# sterownik.net
KiCad netlist of a schematic drawn in EAGLE
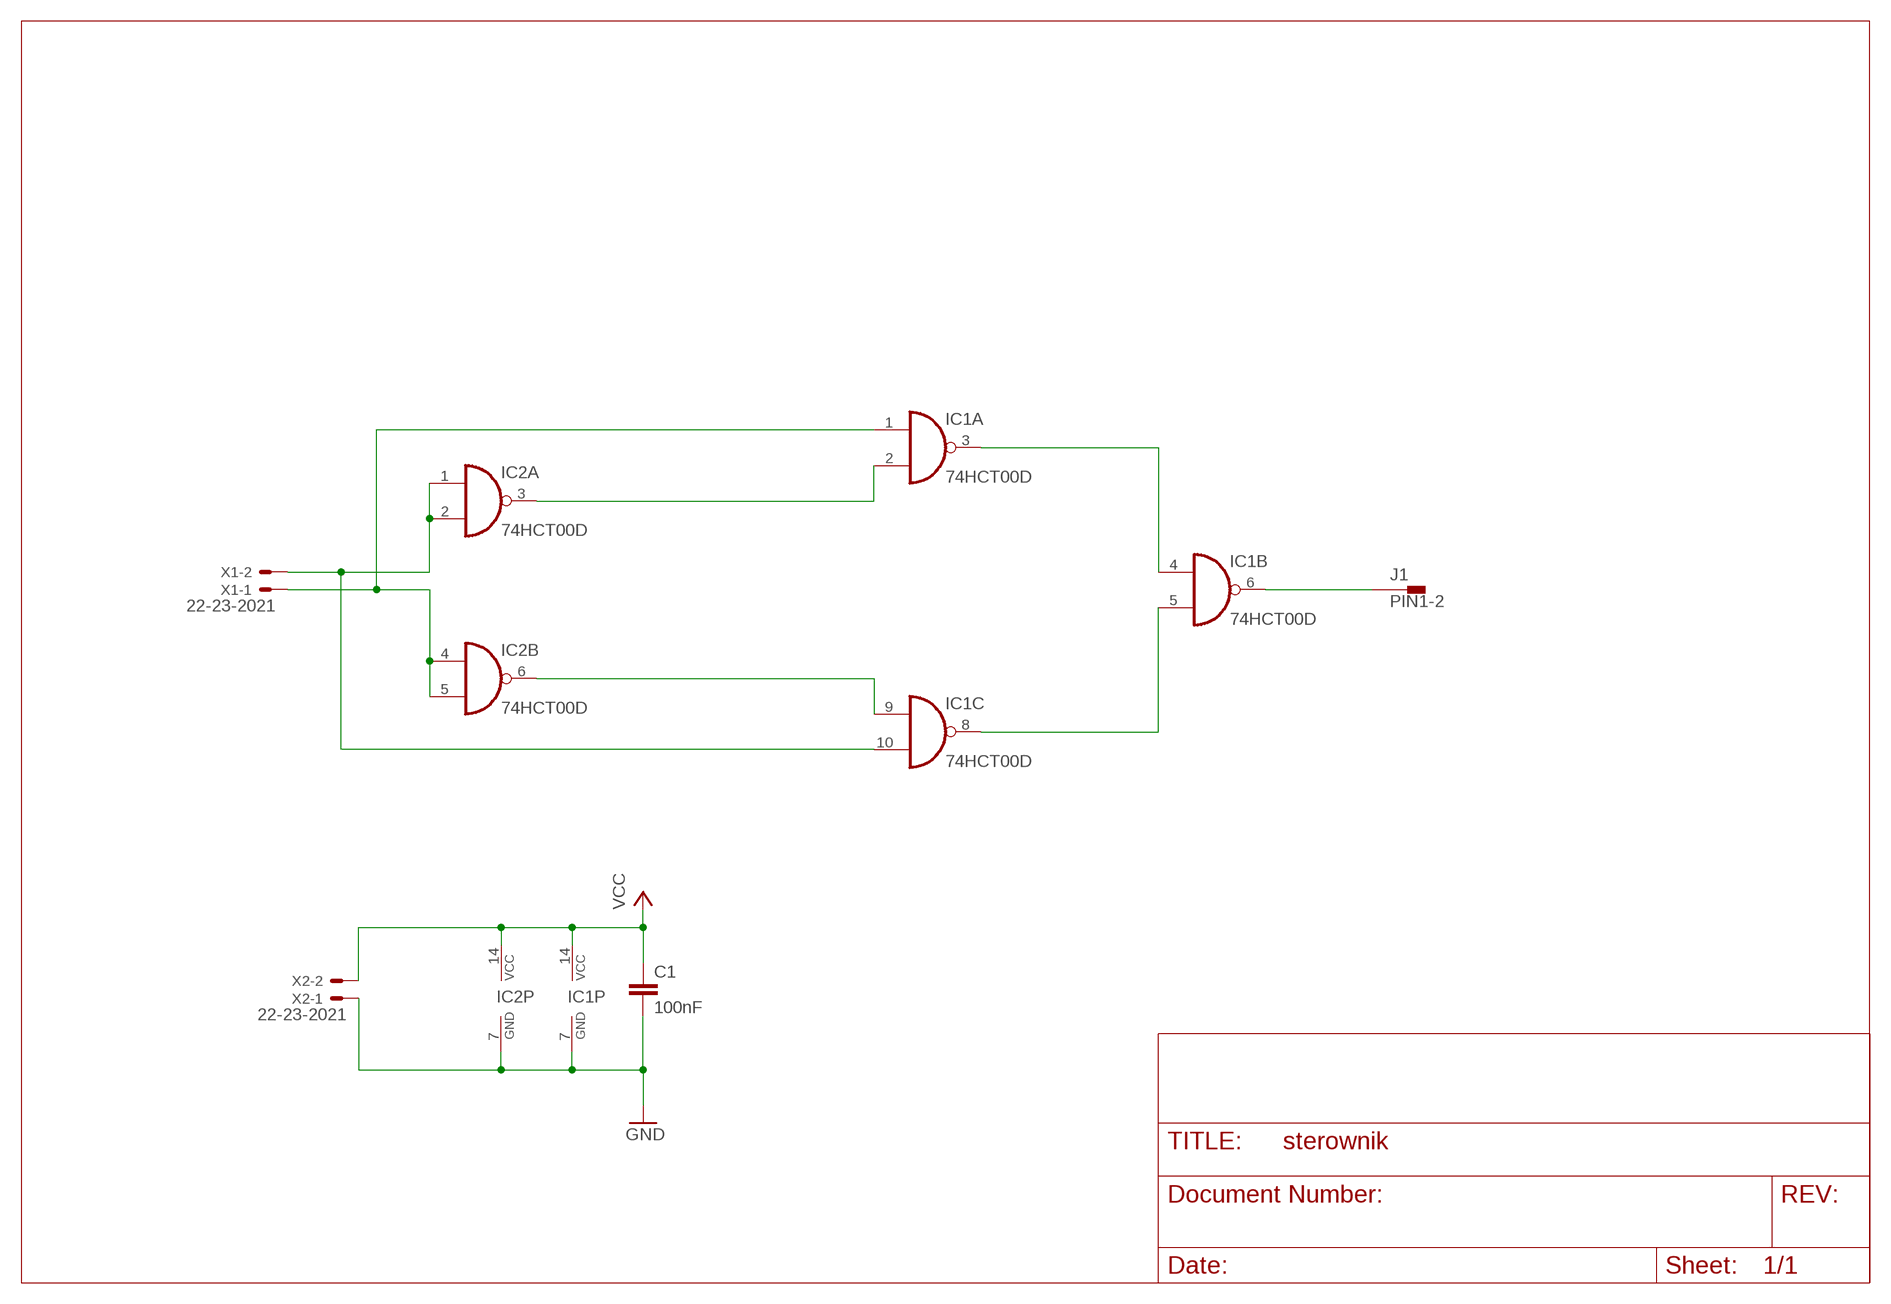
[diagram p0: schematic, sheet 1]

(export (version "E")
  (design (tool "Eeschema 10.0.6"))
  (components
    (comp (ref "C1")
      (value "100nF")
      (footprint "eagle-import:C025-024X044")
      (libsource (lib "eagle-import") (part "C-EU025-024X044"))
    )
    (comp (ref "IC1")
      (value "74HCT00D")
      (footprint "eagle-import:SO14")
      (libsource (lib "eagle-import") (part "7400DHCT"))
    )
    (comp (ref "IC2")
      (value "74HCT00D")
      (footprint "eagle-import:SO14")
      (libsource (lib "eagle-import") (part "7400DHCT"))
    )
    (comp (ref "J1")
      (value "PIN1-2")
      (footprint "eagle-import:62221")
      (fields (field (name "MF") "TYCO ELECTRONICS") (field (name "MPN") "62221-1"))
      (libsource (lib "eagle-import") (part "PIN1-2"))
    )
    (comp (ref "X1")
      (value "22-23-2021")
      (footprint "eagle-import:22-23-2021")
      (fields (field (name "MF") "MOLEX"))
      (libsource (lib "eagle-import") (part "22-23-2021"))
    )
    (comp (ref "X2")
      (value "22-23-2021")
      (footprint "eagle-import:22-23-2021")
      (fields (field (name "MF") "MOLEX"))
      (libsource (lib "eagle-import") (part "22-23-2021"))
    )
  )
  (nets
    (net (code "1") (name "GND") (class "Default")
      (node (ref "C1") (pin "2") (pinfunction "2_2") (pintype "passive"))
      (node (ref "IC1") (pin "7") (pinfunction "GND_7") (pintype "power_in"))
      (node (ref "IC2") (pin "7") (pinfunction "GND_7") (pintype "power_in"))
      (node (ref "X2") (pin "1") (pinfunction "S_1") (pintype "passive"))
    )
    (net (code "2") (name "Net-(IC1A-I0)") (class "Default")
      (node (ref "IC1") (pin "1") (pinfunction "I0_1") (pintype "input"))
      (node (ref "IC2") (pin "4") (pinfunction "I0_4") (pintype "input"))
      (node (ref "IC2") (pin "5") (pinfunction "I1_5") (pintype "input"))
      (node (ref "X1") (pin "1") (pinfunction "S_1") (pintype "passive"))
    )
    (net (code "3") (name "Net-(IC1A-I1)") (class "Default")
      (node (ref "IC1") (pin "2") (pinfunction "I1_2") (pintype "input"))
      (node (ref "IC2") (pin "3") (pinfunction "O_3") (pintype "output"))
    )
    (net (code "4") (name "Net-(IC1A-O)") (class "Default")
      (node (ref "IC1") (pin "3") (pinfunction "O_3") (pintype "output"))
      (node (ref "IC1") (pin "4") (pinfunction "I0_4") (pintype "input"))
    )
    (net (code "5") (name "Net-(IC1B-I1)") (class "Default")
      (node (ref "IC1") (pin "5") (pinfunction "I1_5") (pintype "input"))
      (node (ref "IC1") (pin "8") (pinfunction "O_8") (pintype "output"))
    )
    (net (code "6") (name "Net-(IC1B-O)") (class "Default")
      (node (ref "IC1") (pin "6") (pinfunction "O_6") (pintype "output"))
      (node (ref "J1") (pin "1") (pinfunction "1_1") (pintype "passive"))
    )
    (net (code "7") (name "Net-(IC1C-I0)") (class "Default")
      (node (ref "IC1") (pin "9") (pinfunction "I0_9") (pintype "input"))
      (node (ref "IC2") (pin "6") (pinfunction "O_6") (pintype "output"))
    )
    (net (code "8") (name "Net-(IC1C-I1)") (class "Default")
      (node (ref "IC1") (pin "10") (pinfunction "I1_10") (pintype "input"))
      (node (ref "IC2") (pin "1") (pinfunction "I0_1") (pintype "input"))
      (node (ref "IC2") (pin "2") (pinfunction "I1_2") (pintype "input"))
      (node (ref "X1") (pin "2") (pinfunction "S_2") (pintype "passive"))
    )
    (net (code "9") (name "VCC") (class "Default")
      (node (ref "C1") (pin "1") (pinfunction "1_1") (pintype "passive"))
      (node (ref "IC1") (pin "14") (pinfunction "VCC_14") (pintype "power_in"))
      (node (ref "IC2") (pin "14") (pinfunction "VCC_14") (pintype "power_in"))
      (node (ref "X2") (pin "2") (pinfunction "S_2") (pintype "passive"))
    )
  )
)
